# v3pow.net
KiCad netlist of a schematic drawn in EAGLE
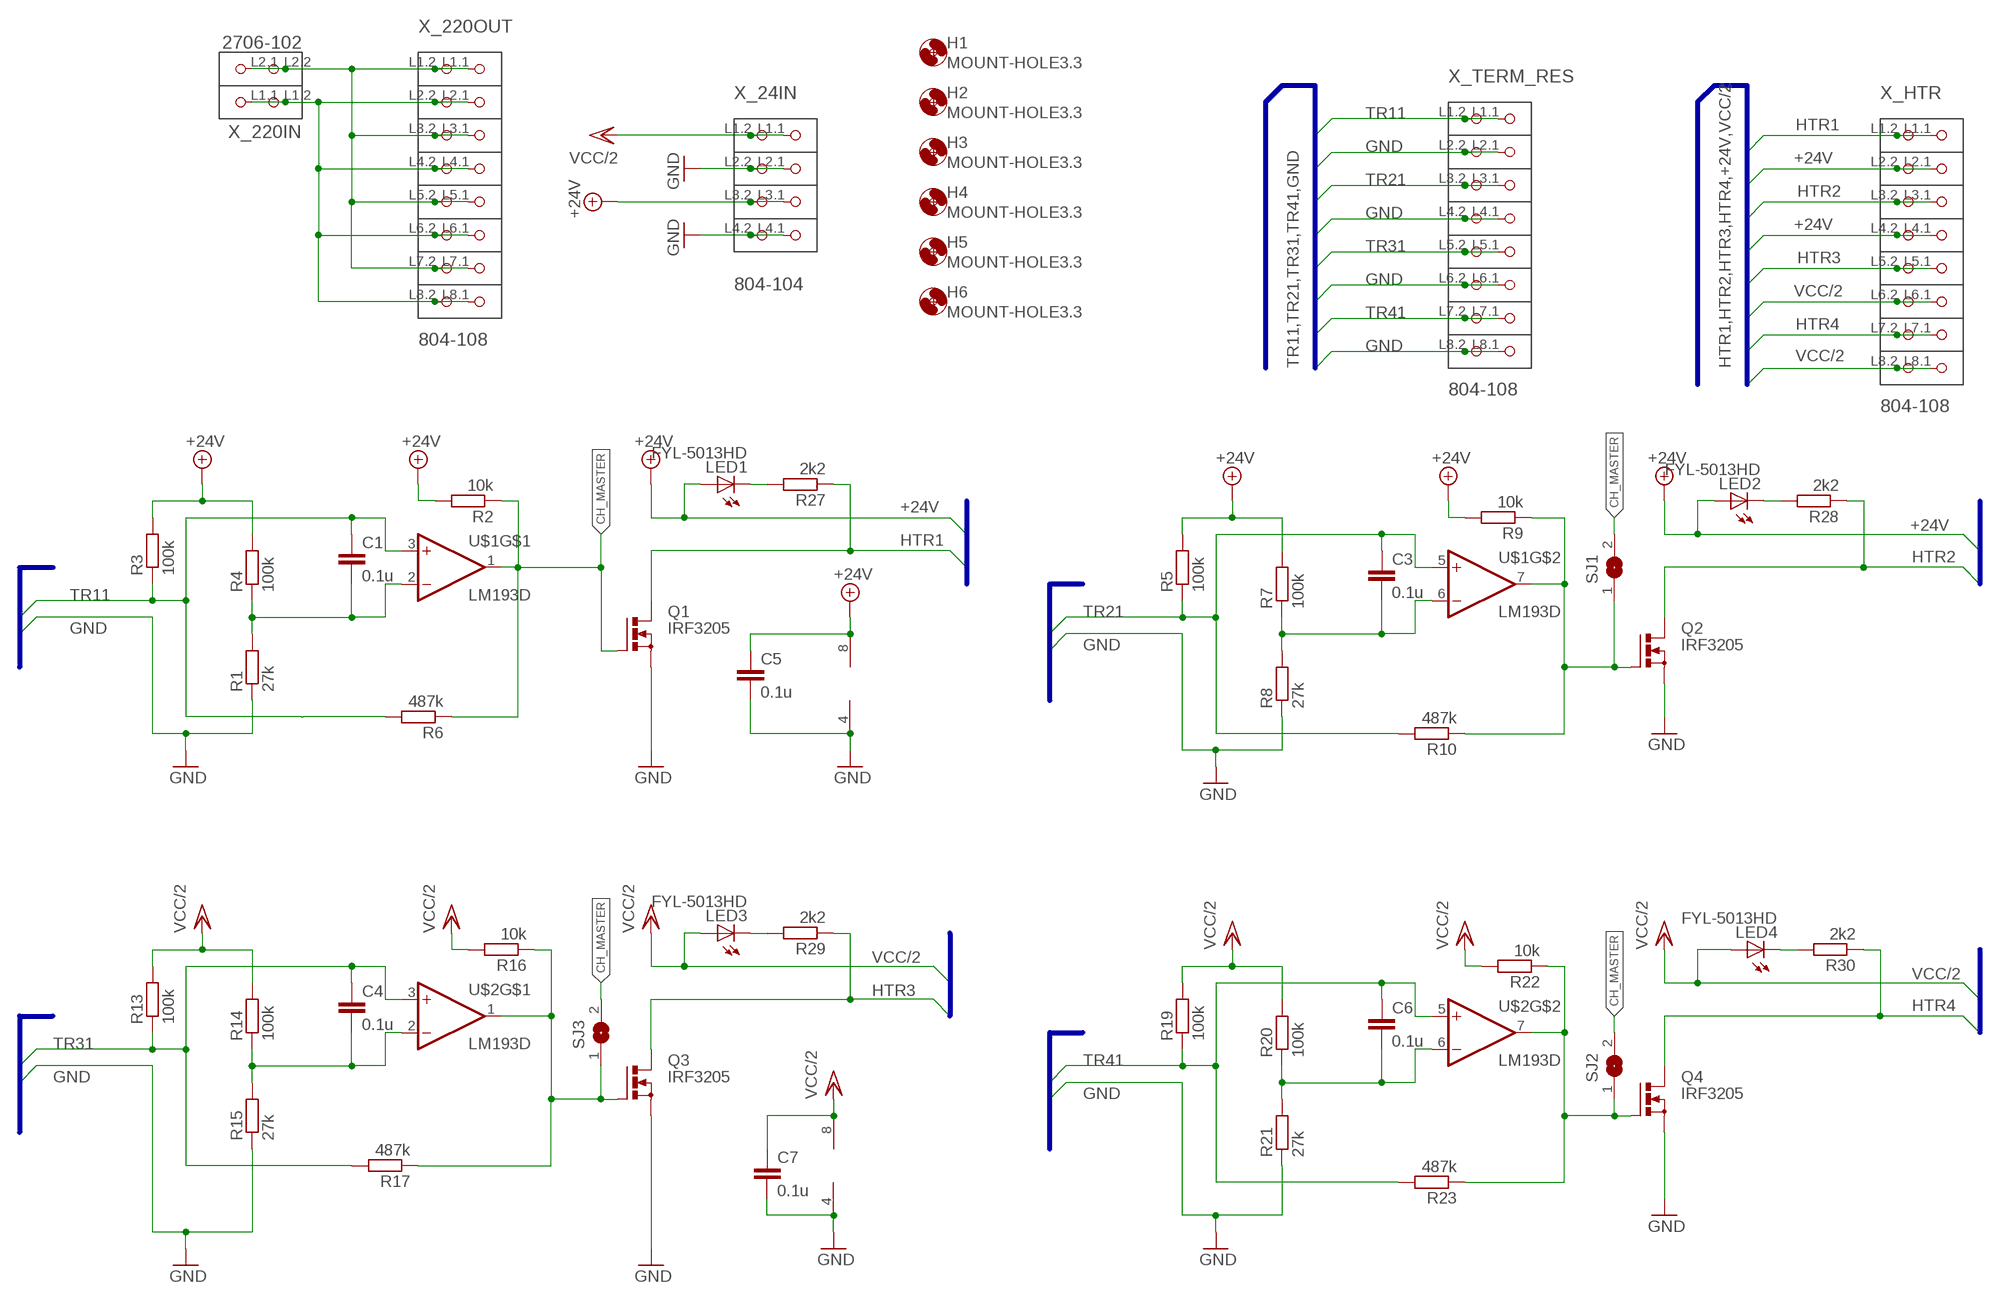
[diagram p0: schematic, sheet 1]

(export (version "E")
  (design (tool "Eeschema 10.0.6"))
  (components
    (comp (ref "C1")
      (value "0.1u")
      (footprint "eagle-import:C0805")
      (libsource (lib "eagle-import") (part "C-EUC0805"))
    )
    (comp (ref "C3")
      (value "0.1u")
      (footprint "eagle-import:C0805")
      (libsource (lib "eagle-import") (part "C-EUC0805"))
    )
    (comp (ref "C4")
      (value "0.1u")
      (footprint "eagle-import:C0805")
      (libsource (lib "eagle-import") (part "C-EUC0805"))
    )
    (comp (ref "C5")
      (value "0.1u")
      (footprint "eagle-import:C0805")
      (libsource (lib "eagle-import") (part "C-EUC0805"))
    )
    (comp (ref "C6")
      (value "0.1u")
      (footprint "eagle-import:C0805")
      (libsource (lib "eagle-import") (part "C-EUC0805"))
    )
    (comp (ref "C7")
      (value "0.1u")
      (footprint "eagle-import:C0805")
      (libsource (lib "eagle-import") (part "C-EUC0805"))
    )
    (comp (ref "H1")
      (value "MOUNT-HOLE3.3")
      (footprint "eagle-import:3,3")
      (libsource (lib "eagle-import") (part "MOUNT-HOLE3.3"))
    )
    (comp (ref "H2")
      (value "MOUNT-HOLE3.3")
      (footprint "eagle-import:3,3")
      (libsource (lib "eagle-import") (part "MOUNT-HOLE3.3"))
    )
    (comp (ref "H3")
      (value "MOUNT-HOLE3.3")
      (footprint "eagle-import:3,3")
      (libsource (lib "eagle-import") (part "MOUNT-HOLE3.3"))
    )
    (comp (ref "H4")
      (value "MOUNT-HOLE3.3")
      (footprint "eagle-import:3,3")
      (libsource (lib "eagle-import") (part "MOUNT-HOLE3.3"))
    )
    (comp (ref "H5")
      (value "MOUNT-HOLE3.3")
      (footprint "eagle-import:3,3")
      (libsource (lib "eagle-import") (part "MOUNT-HOLE3.3"))
    )
    (comp (ref "H6")
      (value "MOUNT-HOLE3.3")
      (footprint "eagle-import:3,3")
      (libsource (lib "eagle-import") (part "MOUNT-HOLE3.3"))
    )
    (comp (ref "LED1")
      (value "FYL-5013HD")
      (footprint "eagle-import:LED5MM")
      (libsource (lib "eagle-import") (part "LED5MM"))
    )
    (comp (ref "LED2")
      (value "FYL-5013HD")
      (footprint "eagle-import:LED5MM")
      (libsource (lib "eagle-import") (part "LED5MM"))
    )
    (comp (ref "LED3")
      (value "FYL-5013HD")
      (footprint "eagle-import:LED5MM")
      (libsource (lib "eagle-import") (part "LED5MM"))
    )
    (comp (ref "LED4")
      (value "FYL-5013HD")
      (footprint "eagle-import:LED5MM")
      (libsource (lib "eagle-import") (part "LED5MM"))
    )
    (comp (ref "Q1")
      (value "IRF3205")
      (footprint "eagle-import:TO220BV")
      (libsource (lib "eagle-import") (part "PMOSFET_NTO220BV"))
    )
    (comp (ref "Q2")
      (value "IRF3205")
      (footprint "eagle-import:TO220BV")
      (libsource (lib "eagle-import") (part "PMOSFET_NTO220BV"))
    )
    (comp (ref "Q3")
      (value "IRF3205")
      (footprint "eagle-import:TO220BV")
      (libsource (lib "eagle-import") (part "PMOSFET_NTO220BV"))
    )
    (comp (ref "Q4")
      (value "IRF3205")
      (footprint "eagle-import:TO220BV")
      (libsource (lib "eagle-import") (part "PMOSFET_NTO220BV"))
    )
    (comp (ref "R1")
      (value "27k")
      (footprint "eagle-import:M0805")
      (libsource (lib "eagle-import") (part "R-EU_M0805"))
    )
    (comp (ref "R2")
      (value "10k")
      (footprint "eagle-import:M0805")
      (libsource (lib "eagle-import") (part "R-EU_M0805"))
    )
    (comp (ref "R3")
      (value "100k")
      (footprint "eagle-import:M0805")
      (libsource (lib "eagle-import") (part "R-EU_M0805"))
    )
    (comp (ref "R4")
      (value "100k")
      (footprint "eagle-import:M0805")
      (libsource (lib "eagle-import") (part "R-EU_M0805"))
    )
    (comp (ref "R5")
      (value "100k")
      (footprint "eagle-import:M0805")
      (libsource (lib "eagle-import") (part "R-EU_M0805"))
    )
    (comp (ref "R6")
      (value "487k")
      (footprint "eagle-import:M0805")
      (libsource (lib "eagle-import") (part "R-EU_M0805"))
    )
    (comp (ref "R7")
      (value "100k")
      (footprint "eagle-import:M0805")
      (libsource (lib "eagle-import") (part "R-EU_M0805"))
    )
    (comp (ref "R8")
      (value "27k")
      (footprint "eagle-import:M0805")
      (libsource (lib "eagle-import") (part "R-EU_M0805"))
    )
    (comp (ref "R9")
      (value "10k")
      (footprint "eagle-import:M0805")
      (libsource (lib "eagle-import") (part "R-EU_M0805"))
    )
    (comp (ref "R10")
      (value "487k")
      (footprint "eagle-import:M0805")
      (libsource (lib "eagle-import") (part "R-EU_M0805"))
    )
    (comp (ref "R13")
      (value "100k")
      (footprint "eagle-import:M0805")
      (libsource (lib "eagle-import") (part "R-EU_M0805"))
    )
    (comp (ref "R14")
      (value "100k")
      (footprint "eagle-import:M0805")
      (libsource (lib "eagle-import") (part "R-EU_M0805"))
    )
    (comp (ref "R15")
      (value "27k")
      (footprint "eagle-import:M0805")
      (libsource (lib "eagle-import") (part "R-EU_M0805"))
    )
    (comp (ref "R16")
      (value "10k")
      (footprint "eagle-import:M0805")
      (libsource (lib "eagle-import") (part "R-EU_M0805"))
    )
    (comp (ref "R17")
      (value "487k")
      (footprint "eagle-import:M0805")
      (libsource (lib "eagle-import") (part "R-EU_M0805"))
    )
    (comp (ref "R19")
      (value "100k")
      (footprint "eagle-import:M0805")
      (libsource (lib "eagle-import") (part "R-EU_M0805"))
    )
    (comp (ref "R20")
      (value "100k")
      (footprint "eagle-import:M0805")
      (libsource (lib "eagle-import") (part "R-EU_M0805"))
    )
    (comp (ref "R21")
      (value "27k")
      (footprint "eagle-import:M0805")
      (libsource (lib "eagle-import") (part "R-EU_M0805"))
    )
    (comp (ref "R22")
      (value "10k")
      (footprint "eagle-import:M0805")
      (libsource (lib "eagle-import") (part "R-EU_M0805"))
    )
    (comp (ref "R23")
      (value "487k")
      (footprint "eagle-import:M0805")
      (libsource (lib "eagle-import") (part "R-EU_M0805"))
    )
    (comp (ref "R27")
      (value "2k2")
      (footprint "eagle-import:M0805")
      (libsource (lib "eagle-import") (part "R-EU_M0805"))
    )
    (comp (ref "R28")
      (value "2k2")
      (footprint "eagle-import:M0805")
      (libsource (lib "eagle-import") (part "R-EU_M0805"))
    )
    (comp (ref "R29")
      (value "2k2")
      (footprint "eagle-import:M0805")
      (libsource (lib "eagle-import") (part "R-EU_M0805"))
    )
    (comp (ref "R30")
      (value "2k2")
      (footprint "eagle-import:M0805")
      (libsource (lib "eagle-import") (part "R-EU_M0805"))
    )
    (comp (ref "SJ1") (value "SJ") (footprint "eagle-import:SJ") (libsource (lib "eagle-import") (part "SJ")))
    (comp (ref "SJ2") (value "SJ") (footprint "eagle-import:SJ") (libsource (lib "eagle-import") (part "SJ")))
    (comp (ref "SJ3") (value "SJ") (footprint "eagle-import:SJ") (libsource (lib "eagle-import") (part "SJ")))
    (comp (ref "U$1")
      (value "LM193D")
      (footprint "eagle-import:SO08")
      (libsource (lib "eagle-import") (part "LM193D"))
    )
    (comp (ref "U$2")
      (value "LM193D")
      (footprint "eagle-import:SO08")
      (libsource (lib "eagle-import") (part "LM193D"))
    )
    (comp (ref "X_24IN")
      (value "804-104")
      (footprint "eagle-import:P-804-104")
      (libsource (lib "eagle-import") (part "804-104"))
    )
    (comp (ref "X_220IN")
      (value "2706-102")
      (footprint "eagle-import:P-2706-102")
      (libsource (lib "eagle-import") (part "2706-102"))
    )
    (comp (ref "X_220OUT")
      (value "804-108")
      (footprint "eagle-import:P-804-108")
      (libsource (lib "eagle-import") (part "804-108"))
    )
    (comp (ref "X_HTR")
      (value "804-108")
      (footprint "eagle-import:P-804-108")
      (libsource (lib "eagle-import") (part "804-108"))
    )
    (comp (ref "X_TERM_RES")
      (value "804-108")
      (footprint "eagle-import:P-804-108")
      (libsource (lib "eagle-import") (part "804-108"))
    )
  )
  (nets
    (net (code "5") (name "+24V") (class "Default")
      (node (ref "C5") (pin "1") (pinfunction "1_1") (pintype "passive"))
      (node (ref "LED1") (pin "A") (pinfunction "A_A") (pintype "passive"))
      (node (ref "LED2") (pin "A") (pinfunction "A_A") (pintype "passive"))
      (node (ref "R2") (pin "2") (pinfunction "2_2") (pintype "passive"))
      (node (ref "R3") (pin "2") (pinfunction "2_2") (pintype "passive"))
      (node (ref "R4") (pin "2") (pinfunction "2_2") (pintype "passive"))
      (node (ref "R5") (pin "2") (pinfunction "2_2") (pintype "passive"))
      (node (ref "R7") (pin "2") (pinfunction "2_2") (pintype "passive"))
      (node (ref "R9") (pin "2") (pinfunction "2_2") (pintype "passive"))
      (node (ref "U$1") (pin "8") (pinfunction "V+_8") (pintype "power_in"))
      (node (ref "X_24IN") (pin "L3.1") (pinfunction "P3.1_L3.1") (pintype "bidirectional"))
      (node (ref "X_24IN") (pin "L3.2") (pinfunction "P3.2_L3.2") (pintype "bidirectional"))
      (node (ref "X_HTR") (pin "L2.1") (pinfunction "P2.1_L2.1") (pintype "bidirectional"))
      (node (ref "X_HTR") (pin "L2.2") (pinfunction "P2.2_L2.2") (pintype "bidirectional"))
      (node (ref "X_HTR") (pin "L4.1") (pinfunction "P4.1_L4.1") (pintype "bidirectional"))
      (node (ref "X_HTR") (pin "L4.2") (pinfunction "P4.2_L4.2") (pintype "bidirectional"))
    )
    (net (code "6") (name "/HTR1") (class "Default")
      (node (ref "Q1") (pin "D") (pinfunction "D_D") (pintype "passive"))
      (node (ref "R27") (pin "1") (pinfunction "1_1") (pintype "passive"))
      (node (ref "X_HTR") (pin "L1.1") (pinfunction "P1.1_L1.1") (pintype "bidirectional"))
      (node (ref "X_HTR") (pin "L1.2") (pinfunction "P1.2_L1.2") (pintype "bidirectional"))
    )
    (net (code "7") (name "/HTR2") (class "Default")
      (node (ref "Q2") (pin "D") (pinfunction "D_D") (pintype "passive"))
      (node (ref "R28") (pin "1") (pinfunction "1_1") (pintype "passive"))
      (node (ref "X_HTR") (pin "L3.1") (pinfunction "P3.1_L3.1") (pintype "bidirectional"))
      (node (ref "X_HTR") (pin "L3.2") (pinfunction "P3.2_L3.2") (pintype "bidirectional"))
    )
    (net (code "8") (name "/HTR3") (class "Default")
      (node (ref "Q3") (pin "D") (pinfunction "D_D") (pintype "passive"))
      (node (ref "R29") (pin "1") (pinfunction "1_1") (pintype "passive"))
      (node (ref "X_HTR") (pin "L5.1") (pinfunction "P5.1_L5.1") (pintype "bidirectional"))
      (node (ref "X_HTR") (pin "L5.2") (pinfunction "P5.2_L5.2") (pintype "bidirectional"))
    )
    (net (code "9") (name "/HTR4") (class "Default")
      (node (ref "Q4") (pin "D") (pinfunction "D_D") (pintype "passive"))
      (node (ref "R30") (pin "1") (pinfunction "1_1") (pintype "passive"))
      (node (ref "X_HTR") (pin "L7.1") (pinfunction "P7.1_L7.1") (pintype "bidirectional"))
      (node (ref "X_HTR") (pin "L7.2") (pinfunction "P7.2_L7.2") (pintype "bidirectional"))
    )
    (net (code "10") (name "/TR11") (class "Default")
      (node (ref "C1") (pin "1") (pinfunction "1_1") (pintype "passive"))
      (node (ref "R3") (pin "1") (pinfunction "1_1") (pintype "passive"))
      (node (ref "R6") (pin "2") (pinfunction "2_2") (pintype "passive"))
      (node (ref "U$1") (pin "3") (pinfunction "+IN_3") (pintype "input"))
      (node (ref "X_TERM_RES") (pin "L1.1") (pinfunction "P1.1_L1.1") (pintype "bidirectional"))
      (node (ref "X_TERM_RES") (pin "L1.2") (pinfunction "P1.2_L1.2") (pintype "bidirectional"))
    )
    (net (code "11") (name "/TR21") (class "Default")
      (node (ref "C3") (pin "1") (pinfunction "1_1") (pintype "passive"))
      (node (ref "R10") (pin "2") (pinfunction "2_2") (pintype "passive"))
      (node (ref "R5") (pin "1") (pinfunction "1_1") (pintype "passive"))
      (node (ref "U$1") (pin "5") (pinfunction "+IN_5") (pintype "input"))
      (node (ref "X_TERM_RES") (pin "L3.1") (pinfunction "P3.1_L3.1") (pintype "bidirectional"))
      (node (ref "X_TERM_RES") (pin "L3.2") (pinfunction "P3.2_L3.2") (pintype "bidirectional"))
    )
    (net (code "12") (name "/TR31") (class "Default")
      (node (ref "C4") (pin "1") (pinfunction "1_1") (pintype "passive"))
      (node (ref "R13") (pin "1") (pinfunction "1_1") (pintype "passive"))
      (node (ref "R17") (pin "2") (pinfunction "2_2") (pintype "passive"))
      (node (ref "U$2") (pin "3") (pinfunction "+IN_3") (pintype "input"))
      (node (ref "X_TERM_RES") (pin "L5.1") (pinfunction "P5.1_L5.1") (pintype "bidirectional"))
      (node (ref "X_TERM_RES") (pin "L5.2") (pinfunction "P5.2_L5.2") (pintype "bidirectional"))
    )
    (net (code "13") (name "/TR41") (class "Default")
      (node (ref "C6") (pin "1") (pinfunction "1_1") (pintype "passive"))
      (node (ref "R19") (pin "1") (pinfunction "1_1") (pintype "passive"))
      (node (ref "R23") (pin "2") (pinfunction "2_2") (pintype "passive"))
      (node (ref "U$2") (pin "5") (pinfunction "+IN_5") (pintype "input"))
      (node (ref "X_TERM_RES") (pin "L7.1") (pinfunction "P7.1_L7.1") (pintype "bidirectional"))
      (node (ref "X_TERM_RES") (pin "L7.2") (pinfunction "P7.2_L7.2") (pintype "bidirectional"))
    )
    (net (code "17") (name "CH_MASTER") (class "Default")
      (node (ref "Q1") (pin "G") (pinfunction "G_G") (pintype "passive"))
      (node (ref "R2") (pin "1") (pinfunction "1_1") (pintype "passive"))
      (node (ref "R6") (pin "1") (pinfunction "1_1") (pintype "passive"))
      (node (ref "SJ1") (pin "2") (pinfunction "2_2") (pintype "passive"))
      (node (ref "SJ2") (pin "2") (pinfunction "2_2") (pintype "passive"))
      (node (ref "SJ3") (pin "2") (pinfunction "2_2") (pintype "passive"))
      (node (ref "U$1") (pin "1") (pinfunction "OUT_1") (pintype "output"))
    )
    (net (code "18") (name "GND") (class "Default")
      (node (ref "C5") (pin "2") (pinfunction "2_2") (pintype "passive"))
      (node (ref "C7") (pin "2") (pinfunction "2_2") (pintype "passive"))
      (node (ref "Q1") (pin "S") (pinfunction "S_S") (pintype "passive"))
      (node (ref "Q2") (pin "S") (pinfunction "S_S") (pintype "passive"))
      (node (ref "Q3") (pin "S") (pinfunction "S_S") (pintype "passive"))
      (node (ref "Q4") (pin "S") (pinfunction "S_S") (pintype "passive"))
      (node (ref "R1") (pin "1") (pinfunction "1_1") (pintype "passive"))
      (node (ref "R15") (pin "1") (pinfunction "1_1") (pintype "passive"))
      (node (ref "R21") (pin "1") (pinfunction "1_1") (pintype "passive"))
      (node (ref "R8") (pin "1") (pinfunction "1_1") (pintype "passive"))
      (node (ref "U$1") (pin "4") (pinfunction "V-_4") (pintype "power_in"))
      (node (ref "U$2") (pin "4") (pinfunction "V-_4") (pintype "power_in"))
      (node (ref "X_24IN") (pin "L2.1") (pinfunction "P2.1_L2.1") (pintype "bidirectional"))
      (node (ref "X_24IN") (pin "L2.2") (pinfunction "P2.2_L2.2") (pintype "bidirectional"))
      (node (ref "X_24IN") (pin "L4.1") (pinfunction "P4.1_L4.1") (pintype "bidirectional"))
      (node (ref "X_24IN") (pin "L4.2") (pinfunction "P4.2_L4.2") (pintype "bidirectional"))
      (node (ref "X_TERM_RES") (pin "L2.1") (pinfunction "P2.1_L2.1") (pintype "bidirectional"))
      (node (ref "X_TERM_RES") (pin "L2.2") (pinfunction "P2.2_L2.2") (pintype "bidirectional"))
      (node (ref "X_TERM_RES") (pin "L4.1") (pinfunction "P4.1_L4.1") (pintype "bidirectional"))
      (node (ref "X_TERM_RES") (pin "L4.2") (pinfunction "P4.2_L4.2") (pintype "bidirectional"))
      (node (ref "X_TERM_RES") (pin "L6.1") (pinfunction "P6.1_L6.1") (pintype "bidirectional"))
      (node (ref "X_TERM_RES") (pin "L6.2") (pinfunction "P6.2_L6.2") (pintype "bidirectional"))
      (node (ref "X_TERM_RES") (pin "L8.1") (pinfunction "P8.1_L8.1") (pintype "bidirectional"))
      (node (ref "X_TERM_RES") (pin "L8.2") (pinfunction "P8.2_L8.2") (pintype "bidirectional"))
    )
    (net (code "19") (name "Net-(LED1-C)") (class "Default")
      (node (ref "LED1") (pin "K") (pinfunction "C_K") (pintype "passive"))
      (node (ref "R27") (pin "2") (pinfunction "2_2") (pintype "passive"))
    )
    (net (code "20") (name "Net-(LED2-C)") (class "Default")
      (node (ref "LED2") (pin "K") (pinfunction "C_K") (pintype "passive"))
      (node (ref "R28") (pin "2") (pinfunction "2_2") (pintype "passive"))
    )
    (net (code "21") (name "Net-(LED3-C)") (class "Default")
      (node (ref "LED3") (pin "K") (pinfunction "C_K") (pintype "passive"))
      (node (ref "R29") (pin "2") (pinfunction "2_2") (pintype "passive"))
    )
    (net (code "22") (name "Net-(LED4-C)") (class "Default")
      (node (ref "LED4") (pin "K") (pinfunction "C_K") (pintype "passive"))
      (node (ref "R30") (pin "2") (pinfunction "2_2") (pintype "passive"))
    )
    (net (code "23") (name "Net-(U$1A--IN)") (class "Default")
      (node (ref "C1") (pin "2") (pinfunction "2_2") (pintype "passive"))
      (node (ref "R1") (pin "2") (pinfunction "2_2") (pintype "passive"))
      (node (ref "R4") (pin "1") (pinfunction "1_1") (pintype "passive"))
      (node (ref "U$1") (pin "2") (pinfunction "-IN_2") (pintype "input"))
    )
    (net (code "24") (name "Net-(U$1B--IN)") (class "Default")
      (node (ref "C3") (pin "2") (pinfunction "2_2") (pintype "passive"))
      (node (ref "R7") (pin "1") (pinfunction "1_1") (pintype "passive"))
      (node (ref "R8") (pin "2") (pinfunction "2_2") (pintype "passive"))
      (node (ref "U$1") (pin "6") (pinfunction "-IN_6") (pintype "input"))
    )
    (net (code "25") (name "Net-(U$1B-OUT)") (class "Default")
      (node (ref "Q2") (pin "G") (pinfunction "G_G") (pintype "passive"))
      (node (ref "R10") (pin "1") (pinfunction "1_1") (pintype "passive"))
      (node (ref "R9") (pin "1") (pinfunction "1_1") (pintype "passive"))
      (node (ref "SJ1") (pin "1") (pinfunction "1_1") (pintype "passive"))
      (node (ref "U$1") (pin "7") (pinfunction "OUT_7") (pintype "output"))
    )
    (net (code "26") (name "Net-(U$2A--IN)") (class "Default")
      (node (ref "C4") (pin "2") (pinfunction "2_2") (pintype "passive"))
      (node (ref "R14") (pin "1") (pinfunction "1_1") (pintype "passive"))
      (node (ref "R15") (pin "2") (pinfunction "2_2") (pintype "passive"))
      (node (ref "U$2") (pin "2") (pinfunction "-IN_2") (pintype "input"))
    )
    (net (code "27") (name "Net-(U$2A-OUT)") (class "Default")
      (node (ref "Q3") (pin "G") (pinfunction "G_G") (pintype "passive"))
      (node (ref "R16") (pin "1") (pinfunction "1_1") (pintype "passive"))
      (node (ref "R17") (pin "1") (pinfunction "1_1") (pintype "passive"))
      (node (ref "SJ3") (pin "1") (pinfunction "1_1") (pintype "passive"))
      (node (ref "U$2") (pin "1") (pinfunction "OUT_1") (pintype "output"))
    )
    (net (code "28") (name "Net-(U$2B--IN)") (class "Default")
      (node (ref "C6") (pin "2") (pinfunction "2_2") (pintype "passive"))
      (node (ref "R20") (pin "1") (pinfunction "1_1") (pintype "passive"))
      (node (ref "R21") (pin "2") (pinfunction "2_2") (pintype "passive"))
      (node (ref "U$2") (pin "6") (pinfunction "-IN_6") (pintype "input"))
    )
    (net (code "29") (name "Net-(U$2B-OUT)") (class "Default")
      (node (ref "Q4") (pin "G") (pinfunction "G_G") (pintype "passive"))
      (node (ref "R22") (pin "1") (pinfunction "1_1") (pintype "passive"))
      (node (ref "R23") (pin "1") (pinfunction "1_1") (pintype "passive"))
      (node (ref "SJ2") (pin "1") (pinfunction "1_1") (pintype "passive"))
      (node (ref "U$2") (pin "7") (pinfunction "OUT_7") (pintype "output"))
    )
    (net (code "30") (name "Net-(X_220IN-P1.1)") (class "Default")
      (node (ref "X_220IN") (pin "L1.1") (pinfunction "P1.1_L1.1") (pintype "bidirectional"))
      (node (ref "X_220IN") (pin "L1.2") (pinfunction "P1.2_L1.2") (pintype "bidirectional"))
      (node (ref "X_220OUT") (pin "L2.1") (pinfunction "P2.1_L2.1") (pintype "bidirectional"))
      (node (ref "X_220OUT") (pin "L2.2") (pinfunction "P2.2_L2.2") (pintype "bidirectional"))
      (node (ref "X_220OUT") (pin "L4.1") (pinfunction "P4.1_L4.1") (pintype "bidirectional"))
      (node (ref "X_220OUT") (pin "L4.2") (pinfunction "P4.2_L4.2") (pintype "bidirectional"))
      (node (ref "X_220OUT") (pin "L6.1") (pinfunction "P6.1_L6.1") (pintype "bidirectional"))
      (node (ref "X_220OUT") (pin "L6.2") (pinfunction "P6.2_L6.2") (pintype "bidirectional"))
      (node (ref "X_220OUT") (pin "L8.1") (pinfunction "P8.1_L8.1") (pintype "bidirectional"))
      (node (ref "X_220OUT") (pin "L8.2") (pinfunction "P8.2_L8.2") (pintype "bidirectional"))
    )
    (net (code "31") (name "Net-(X_220IN-P2.1)") (class "Default")
      (node (ref "X_220IN") (pin "L2.1") (pinfunction "P2.1_L2.1") (pintype "bidirectional"))
      (node (ref "X_220IN") (pin "L2.2") (pinfunction "P2.2_L2.2") (pintype "bidirectional"))
      (node (ref "X_220OUT") (pin "L1.1") (pinfunction "P1.1_L1.1") (pintype "bidirectional"))
      (node (ref "X_220OUT") (pin "L1.2") (pinfunction "P1.2_L1.2") (pintype "bidirectional"))
      (node (ref "X_220OUT") (pin "L3.1") (pinfunction "P3.1_L3.1") (pintype "bidirectional"))
      (node (ref "X_220OUT") (pin "L3.2") (pinfunction "P3.2_L3.2") (pintype "bidirectional"))
      (node (ref "X_220OUT") (pin "L5.1") (pinfunction "P5.1_L5.1") (pintype "bidirectional"))
      (node (ref "X_220OUT") (pin "L5.2") (pinfunction "P5.2_L5.2") (pintype "bidirectional"))
      (node (ref "X_220OUT") (pin "L7.1") (pinfunction "P7.1_L7.1") (pintype "bidirectional"))
      (node (ref "X_220OUT") (pin "L7.2") (pinfunction "P7.2_L7.2") (pintype "bidirectional"))
    )
    (net (code "32") (name "VCC{slash}2") (class "Default")
      (node (ref "C7") (pin "1") (pinfunction "1_1") (pintype "passive"))
      (node (ref "LED3") (pin "A") (pinfunction "A_A") (pintype "passive"))
      (node (ref "LED4") (pin "A") (pinfunction "A_A") (pintype "passive"))
      (node (ref "R13") (pin "2") (pinfunction "2_2") (pintype "passive"))
      (node (ref "R14") (pin "2") (pinfunction "2_2") (pintype "passive"))
      (node (ref "R16") (pin "2") (pinfunction "2_2") (pintype "passive"))
      (node (ref "R19") (pin "2") (pinfunction "2_2") (pintype "passive"))
      (node (ref "R20") (pin "2") (pinfunction "2_2") (pintype "passive"))
      (node (ref "R22") (pin "2") (pinfunction "2_2") (pintype "passive"))
      (node (ref "U$2") (pin "8") (pinfunction "V+_8") (pintype "power_in"))
      (node (ref "X_24IN") (pin "L1.1") (pinfunction "P1.1_L1.1") (pintype "bidirectional"))
      (node (ref "X_24IN") (pin "L1.2") (pinfunction "P1.2_L1.2") (pintype "bidirectional"))
      (node (ref "X_HTR") (pin "L6.1") (pinfunction "P6.1_L6.1") (pintype "bidirectional"))
      (node (ref "X_HTR") (pin "L6.2") (pinfunction "P6.2_L6.2") (pintype "bidirectional"))
      (node (ref "X_HTR") (pin "L8.1") (pinfunction "P8.1_L8.1") (pintype "bidirectional"))
      (node (ref "X_HTR") (pin "L8.2") (pinfunction "P8.2_L8.2") (pintype "bidirectional"))
    )
  )
)
